# serbest.net
KiCad netlist of a schematic drawn in EAGLE
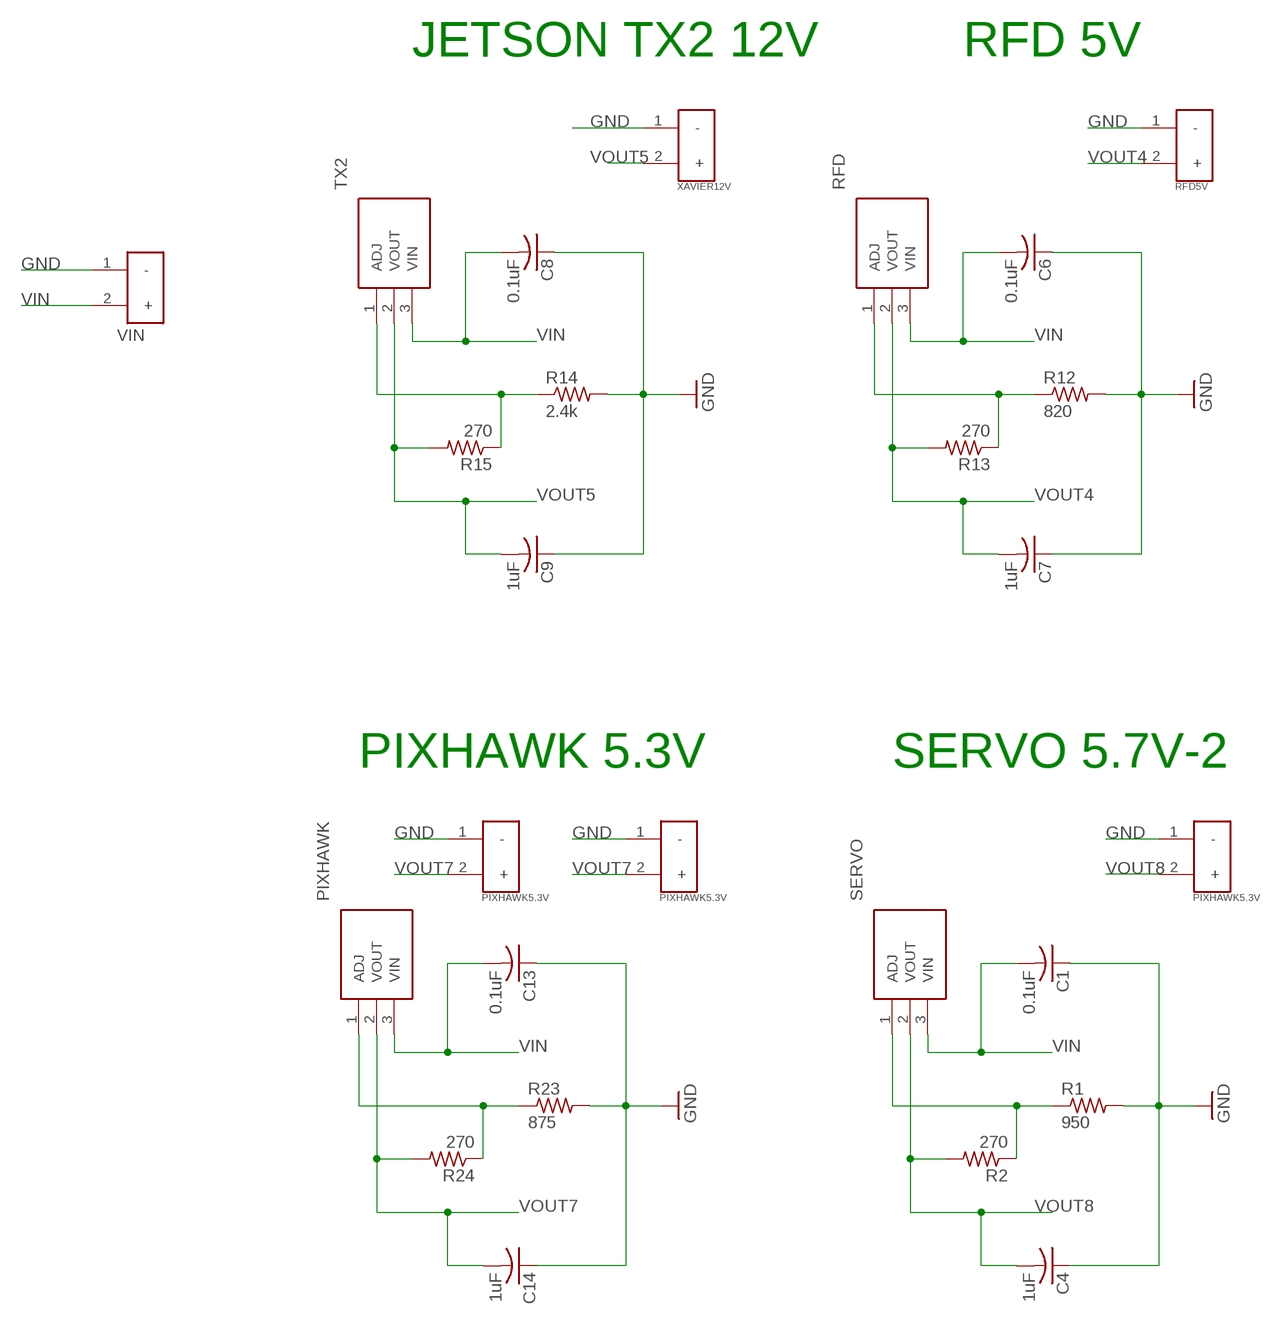
[diagram p0: schematic, sheet 1]

(export (version "E")
  (design (tool "Eeschema 10.0.6"))
  (components
    (comp (ref "C1")
      (value "0.1uF")
      (footprint "eagle-import:C0402K")
      (libsource (lib "eagle-import") (part "C-USC0402K"))
    )
    (comp (ref "C4")
      (value "1uF")
      (footprint "eagle-import:C0402K")
      (libsource (lib "eagle-import") (part "C-USC0402K"))
    )
    (comp (ref "C6")
      (value "0.1uF")
      (footprint "eagle-import:C0402K")
      (libsource (lib "eagle-import") (part "C-USC0402K"))
    )
    (comp (ref "C7")
      (value "1uF")
      (footprint "eagle-import:C0402K")
      (libsource (lib "eagle-import") (part "C-USC0402K"))
    )
    (comp (ref "C8")
      (value "0.1uF")
      (footprint "eagle-import:C0402K")
      (libsource (lib "eagle-import") (part "C-USC0402K"))
    )
    (comp (ref "C9")
      (value "1uF")
      (footprint "eagle-import:C0402K")
      (libsource (lib "eagle-import") (part "C-USC0402K"))
    )
    (comp (ref "C13")
      (value "0.1uF")
      (footprint "eagle-import:C0402K")
      (libsource (lib "eagle-import") (part "C-USC0402K"))
    )
    (comp (ref "C14")
      (value "1uF")
      (footprint "eagle-import:C0402K")
      (libsource (lib "eagle-import") (part "C-USC0402K"))
    )
    (comp (ref "J3")
      (value "VIN")
      (footprint "eagle-import:AMASS_XT60-M")
      (fields (field (name "MF") "AMASS") (field (name "MP") "XT60-M"))
      (libsource (lib "eagle-import") (part "XT60-M"))
    )
    (comp (ref "PIXHAWK")
      (value "PIXHAWK")
      (footprint "eagle-import:TO254P470X1028X1955-3P")
      (fields
        (field (name "ARROW_PART_NUMBER") "LM338T/NOPB")
        (field (name "MOUSER_PART_NUMBER") "926-LM338T/NOPB")
      )
      (libsource (lib "eagle-import") (part "LM338T_NOPB"))
    )
    (comp (ref "PIXHAWK5.3V-1")
      (value "PIXHAWK5.3V")
      (footprint "eagle-import:AMASS_XT60-M")
      (fields (field (name "MF") "AMASS") (field (name "MP") "XT60-M"))
      (libsource (lib "eagle-import") (part "XT60-M"))
    )
    (comp (ref "PIXHAWK5.3V-2")
      (value "PIXHAWK5.3V")
      (footprint "eagle-import:AMASS_XT60-M")
      (fields (field (name "MF") "AMASS") (field (name "MP") "XT60-M"))
      (libsource (lib "eagle-import") (part "XT60-M"))
    )
    (comp (ref "R1")
      (value "950")
      (footprint "eagle-import:R0805")
      (libsource (lib "eagle-import") (part "R-US_R0805"))
    )
    (comp (ref "R2")
      (value "270")
      (footprint "eagle-import:R0805")
      (libsource (lib "eagle-import") (part "R-US_R0805"))
    )
    (comp (ref "R12")
      (value "820")
      (footprint "eagle-import:R0805")
      (libsource (lib "eagle-import") (part "R-US_R0805"))
    )
    (comp (ref "R13")
      (value "270")
      (footprint "eagle-import:R0805")
      (libsource (lib "eagle-import") (part "R-US_R0805"))
    )
    (comp (ref "R14")
      (value "2.4k")
      (footprint "eagle-import:R0805")
      (libsource (lib "eagle-import") (part "R-US_R0805"))
    )
    (comp (ref "R15")
      (value "270")
      (footprint "eagle-import:R0805")
      (libsource (lib "eagle-import") (part "R-US_R0805"))
    )
    (comp (ref "R23")
      (value "875")
      (footprint "eagle-import:R0805")
      (libsource (lib "eagle-import") (part "R-US_R0805"))
    )
    (comp (ref "R24")
      (value "270")
      (footprint "eagle-import:R0805")
      (libsource (lib "eagle-import") (part "R-US_R0805"))
    )
    (comp (ref "RFD")
      (value "RFD")
      (footprint "eagle-import:TO254P470X1028X1955-3P")
      (fields
        (field (name "ARROW_PART_NUMBER") "LM338T/NOPB")
        (field (name "MOUSER_PART_NUMBER") "926-LM338T/NOPB")
      )
      (libsource (lib "eagle-import") (part "LM338T_NOPB"))
    )
    (comp (ref "RFD5V")
      (value "RFD5V")
      (footprint "eagle-import:AMASS_XT60-M")
      (fields (field (name "MF") "AMASS") (field (name "MP") "XT60-M"))
      (libsource (lib "eagle-import") (part "XT60-M"))
    )
    (comp (ref "SERVO-2")
      (value "SERVO")
      (footprint "eagle-import:TO254P470X1028X1955-3P")
      (fields
        (field (name "ARROW_PART_NUMBER") "LM338T/NOPB")
        (field (name "MOUSER_PART_NUMBER") "926-LM338T/NOPB")
      )
      (libsource (lib "eagle-import") (part "LM338T_NOPB"))
    )
    (comp (ref "SERVO5.7V-2")
      (value "PIXHAWK5.3V")
      (footprint "eagle-import:AMASS_XT60-M")
      (fields (field (name "MF") "AMASS") (field (name "MP") "XT60-M"))
      (libsource (lib "eagle-import") (part "XT60-M"))
    )
    (comp (ref "TX2")
      (value "TX2")
      (footprint "eagle-import:TO254P470X1028X1955-3P")
      (fields
        (field (name "ARROW_PART_NUMBER") "LM338T/NOPB")
        (field (name "MOUSER_PART_NUMBER") "926-LM338T/NOPB")
      )
      (libsource (lib "eagle-import") (part "LM338T_NOPB"))
    )
    (comp (ref "TX2-12V")
      (value "XAVIER12V")
      (footprint "eagle-import:AMASS_XT60-M")
      (fields (field (name "MF") "AMASS") (field (name "MP") "XT60-M"))
      (libsource (lib "eagle-import") (part "XT60-M"))
    )
  )
  (nets
    (net (code "1") (name "/VIN") (class "Default")
      (node (ref "C1") (pin "2") (pinfunction "2_2") (pintype "passive"))
      (node (ref "C13") (pin "2") (pinfunction "2_2") (pintype "passive"))
      (node (ref "C6") (pin "2") (pinfunction "2_2") (pintype "passive"))
      (node (ref "C8") (pin "2") (pinfunction "2_2") (pintype "passive"))
      (node (ref "J3") (pin "2") (pinfunction "+_2") (pintype "passive"))
      (node (ref "PIXHAWK") (pin "3") (pinfunction "VIN_3") (pintype "bidirectional"))
      (node (ref "RFD") (pin "3") (pinfunction "VIN_3") (pintype "bidirectional"))
      (node (ref "SERVO-2") (pin "3") (pinfunction "VIN_3") (pintype "bidirectional"))
      (node (ref "TX2") (pin "3") (pinfunction "VIN_3") (pintype "bidirectional"))
    )
    (net (code "2") (name "/VOUT4") (class "Default")
      (node (ref "C7") (pin "2") (pinfunction "2_2") (pintype "passive"))
      (node (ref "R13") (pin "2") (pinfunction "2_2") (pintype "passive"))
      (node (ref "RFD") (pin "2") (pinfunction "VOUT_2") (pintype "bidirectional"))
      (node (ref "RFD5V") (pin "2") (pinfunction "+_2") (pintype "passive"))
    )
    (net (code "3") (name "/VOUT5") (class "Default")
      (node (ref "C9") (pin "2") (pinfunction "2_2") (pintype "passive"))
      (node (ref "R15") (pin "2") (pinfunction "2_2") (pintype "passive"))
      (node (ref "TX2") (pin "2") (pinfunction "VOUT_2") (pintype "bidirectional"))
      (node (ref "TX2-12V") (pin "2") (pinfunction "+_2") (pintype "passive"))
    )
    (net (code "4") (name "/VOUT7") (class "Default")
      (node (ref "C14") (pin "2") (pinfunction "2_2") (pintype "passive"))
      (node (ref "PIXHAWK") (pin "2") (pinfunction "VOUT_2") (pintype "bidirectional"))
      (node (ref "PIXHAWK5.3V-1") (pin "2") (pinfunction "+_2") (pintype "passive"))
      (node (ref "PIXHAWK5.3V-2") (pin "2") (pinfunction "+_2") (pintype "passive"))
      (node (ref "R24") (pin "2") (pinfunction "2_2") (pintype "passive"))
    )
    (net (code "5") (name "/VOUT8") (class "Default")
      (node (ref "C4") (pin "2") (pinfunction "2_2") (pintype "passive"))
      (node (ref "R2") (pin "2") (pinfunction "2_2") (pintype "passive"))
      (node (ref "SERVO-2") (pin "2") (pinfunction "VOUT_2") (pintype "bidirectional"))
      (node (ref "SERVO5.7V-2") (pin "2") (pinfunction "+_2") (pintype "passive"))
    )
    (net (code "6") (name "GND") (class "Default")
      (node (ref "C1") (pin "1") (pinfunction "1_1") (pintype "passive"))
      (node (ref "C13") (pin "1") (pinfunction "1_1") (pintype "passive"))
      (node (ref "C14") (pin "1") (pinfunction "1_1") (pintype "passive"))
      (node (ref "C4") (pin "1") (pinfunction "1_1") (pintype "passive"))
      (node (ref "C6") (pin "1") (pinfunction "1_1") (pintype "passive"))
      (node (ref "C7") (pin "1") (pinfunction "1_1") (pintype "passive"))
      (node (ref "C8") (pin "1") (pinfunction "1_1") (pintype "passive"))
      (node (ref "C9") (pin "1") (pinfunction "1_1") (pintype "passive"))
      (node (ref "J3") (pin "1") (pinfunction "-_1") (pintype "passive"))
      (node (ref "PIXHAWK5.3V-1") (pin "1") (pinfunction "-_1") (pintype "passive"))
      (node (ref "PIXHAWK5.3V-2") (pin "1") (pinfunction "-_1") (pintype "passive"))
      (node (ref "R1") (pin "2") (pinfunction "2_2") (pintype "passive"))
      (node (ref "R12") (pin "2") (pinfunction "2_2") (pintype "passive"))
      (node (ref "R14") (pin "2") (pinfunction "2_2") (pintype "passive"))
      (node (ref "R23") (pin "2") (pinfunction "2_2") (pintype "passive"))
      (node (ref "RFD5V") (pin "1") (pinfunction "-_1") (pintype "passive"))
      (node (ref "SERVO5.7V-2") (pin "1") (pinfunction "-_1") (pintype "passive"))
      (node (ref "TX2-12V") (pin "1") (pinfunction "-_1") (pintype "passive"))
    )
    (net (code "7") (name "Net-(PIXHAWK-ADJ)") (class "Default")
      (node (ref "PIXHAWK") (pin "1") (pinfunction "ADJ_1") (pintype "bidirectional"))
      (node (ref "R23") (pin "1") (pinfunction "1_1") (pintype "passive"))
      (node (ref "R24") (pin "1") (pinfunction "1_1") (pintype "passive"))
    )
    (net (code "8") (name "Net-(RFD-ADJ)") (class "Default")
      (node (ref "R12") (pin "1") (pinfunction "1_1") (pintype "passive"))
      (node (ref "R13") (pin "1") (pinfunction "1_1") (pintype "passive"))
      (node (ref "RFD") (pin "1") (pinfunction "ADJ_1") (pintype "bidirectional"))
    )
    (net (code "9") (name "Net-(SERVO-2-ADJ)") (class "Default")
      (node (ref "R1") (pin "1") (pinfunction "1_1") (pintype "passive"))
      (node (ref "R2") (pin "1") (pinfunction "1_1") (pintype "passive"))
      (node (ref "SERVO-2") (pin "1") (pinfunction "ADJ_1") (pintype "bidirectional"))
    )
    (net (code "10") (name "Net-(TX2-ADJ)") (class "Default")
      (node (ref "R14") (pin "1") (pinfunction "1_1") (pintype "passive"))
      (node (ref "R15") (pin "1") (pinfunction "1_1") (pintype "passive"))
      (node (ref "TX2") (pin "1") (pinfunction "ADJ_1") (pintype "bidirectional"))
    )
  )
)
